# USB_Mini.net
KiCad netlist of a schematic drawn in Altium Designer
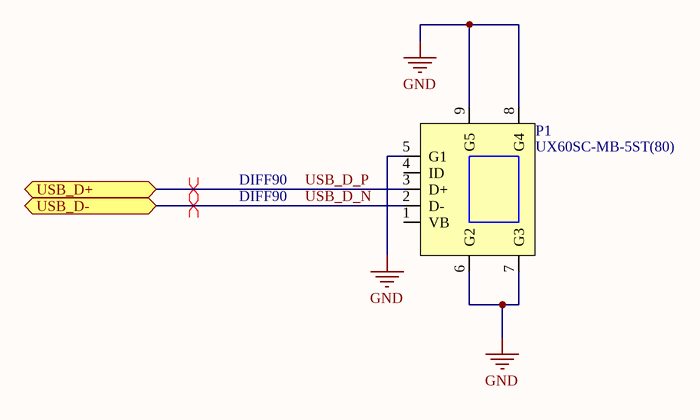
[diagram p0: USB_Mini.SchDoc]

(export (version "E")
  (design (tool "Eeschema 10.0.6"))
  (components
    (comp (ref "P1")
      (value "*")
      (footprint "UX60SC-MB-5ST(80)")
      (description "CONN RCPT USB MINI B R/A SMD")
      (fields (field (name "MPN") "UX60SC-MB-5ST(80)"))
      (libsource (lib "Connector") (part "UX60SC-MB-5ST(80)"))
    )
  )
  (nets
    (net (code "1") (name "/USB_D_N") (class "Default")
      (node (ref "P1") (pin "2") (pinfunction "D-_2") (pintype "passive"))
    )
    (net (code "2") (name "/USB_D_P") (class "Default")
      (node (ref "P1") (pin "3") (pinfunction "D+_3") (pintype "passive"))
    )
    (net (code "3") (name "GND") (class "Default")
      (node (ref "P1") (pin "5") (pinfunction "G1_5") (pintype "passive"))
      (node (ref "P1") (pin "6") (pinfunction "G2_6") (pintype "passive"))
      (node (ref "P1") (pin "7") (pinfunction "G3_7") (pintype "passive"))
      (node (ref "P1") (pin "8") (pinfunction "G4_8") (pintype "passive"))
      (node (ref "P1") (pin "9") (pinfunction "G5_9") (pintype "passive"))
    )
    (net (code "4") (name "unconnected-(P1-ID-Pad4)") (class "Default")
      (node (ref "P1") (pin "4") (pinfunction "ID_4") (pintype "passive"))
    )
    (net (code "5") (name "unconnected-(P1-VB-Pad1)") (class "Default")
      (node (ref "P1") (pin "1") (pinfunction "VB_1") (pintype "passive"))
    )
  )
)
